# motordriver.net
KiCad netlist of a schematic drawn in EAGLE
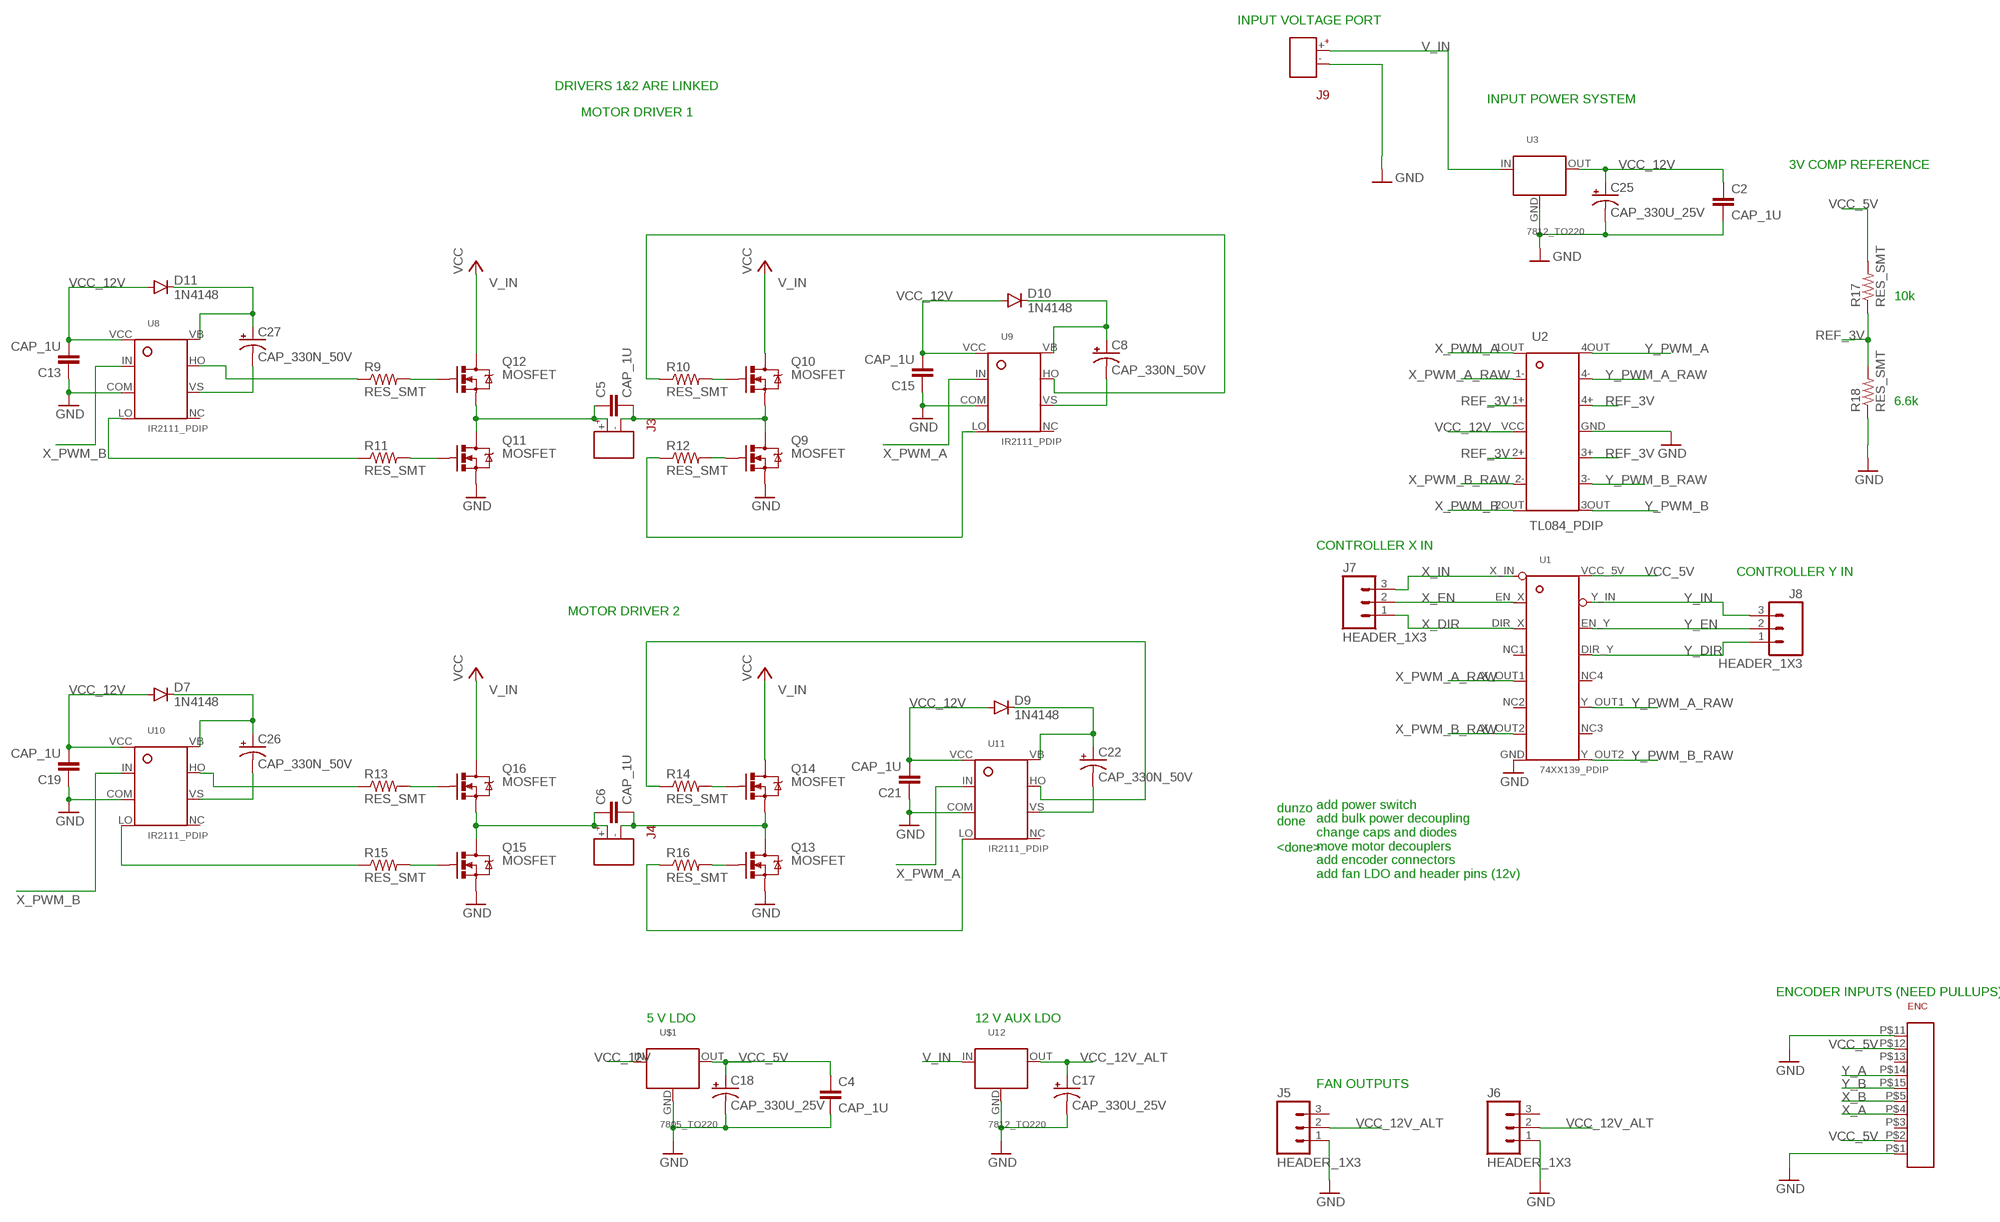
[diagram p0: schematic, sheet 1, part 1 of 2]
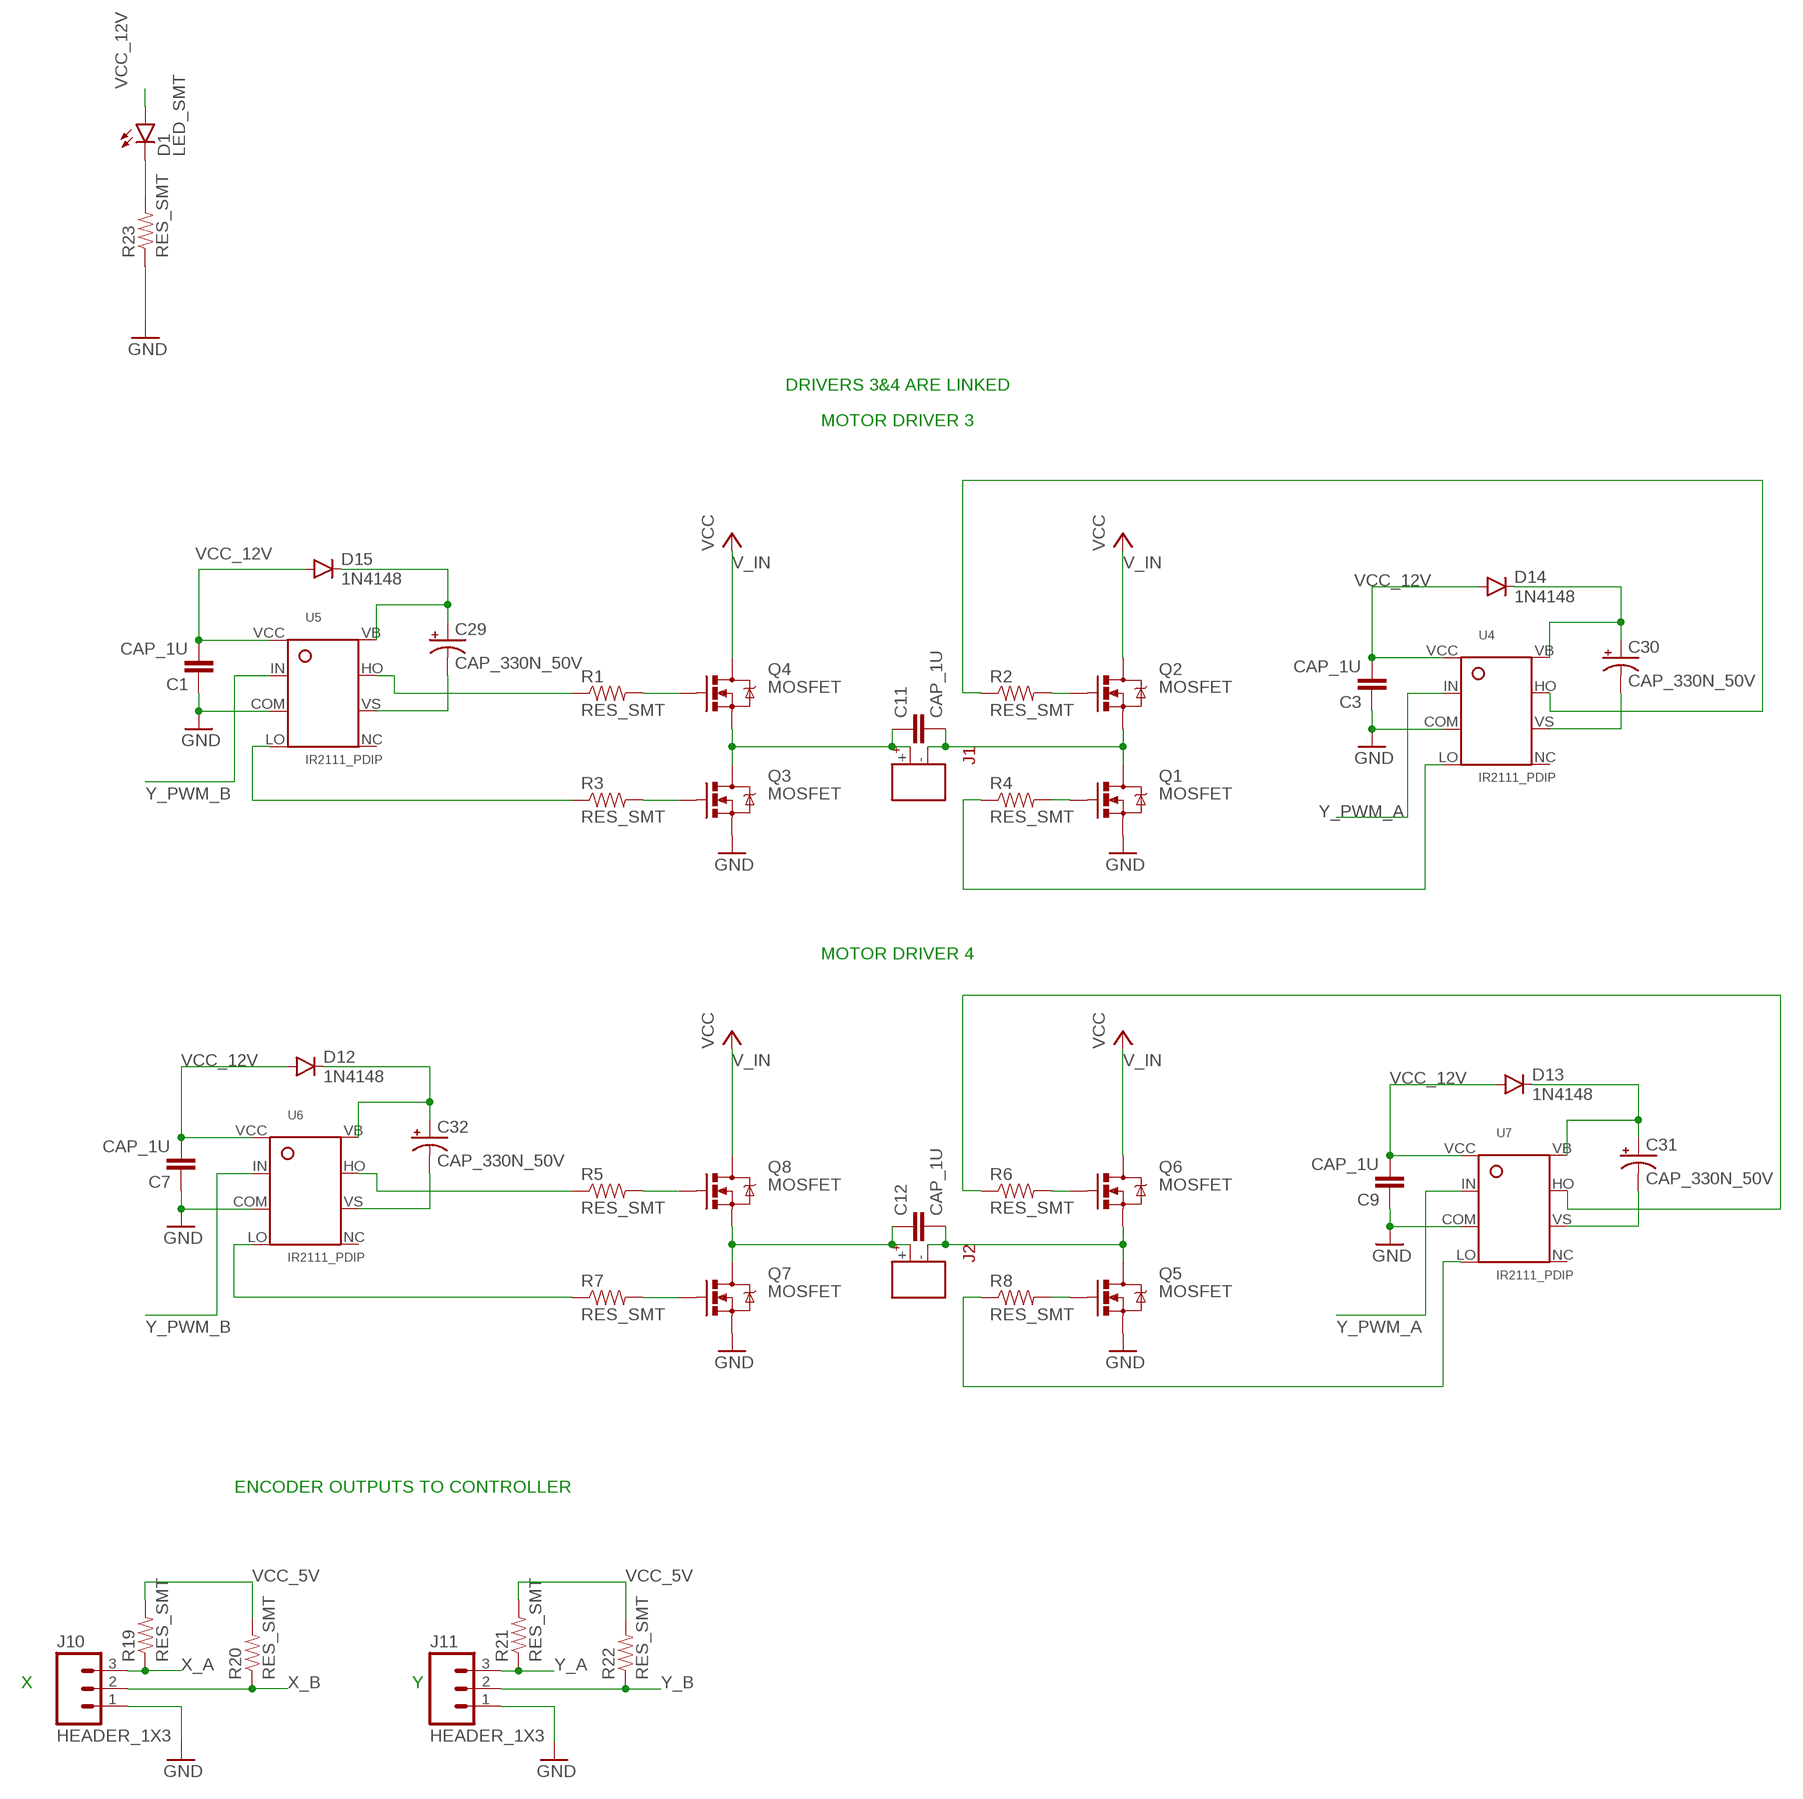
[diagram p1: schematic, sheet 1, part 2 of 2]

(export (version "E")
  (design (tool "Eeschema 10.0.6"))
  (components
    (comp (ref "C1")
      (value "CAP_1U")
      (footprint "eagle-import:2DIP")
      (libsource (lib "eagle-import") (part "CAP_1U"))
    )
    (comp (ref "C2")
      (value "CAP_1U")
      (footprint "eagle-import:2DIP")
      (libsource (lib "eagle-import") (part "CAP_1U"))
    )
    (comp (ref "C3")
      (value "CAP_1U")
      (footprint "eagle-import:2DIP")
      (libsource (lib "eagle-import") (part "CAP_1U"))
    )
    (comp (ref "C4")
      (value "CAP_1U")
      (footprint "eagle-import:2DIP")
      (libsource (lib "eagle-import") (part "CAP_1U"))
    )
    (comp (ref "C5")
      (value "CAP_1U")
      (footprint "eagle-import:2DIP")
      (libsource (lib "eagle-import") (part "CAP_1U"))
    )
    (comp (ref "C6")
      (value "CAP_1U")
      (footprint "eagle-import:2DIP")
      (libsource (lib "eagle-import") (part "CAP_1U"))
    )
    (comp (ref "C7")
      (value "CAP_1U")
      (footprint "eagle-import:2DIP")
      (libsource (lib "eagle-import") (part "CAP_1U"))
    )
    (comp (ref "C8")
      (value "CAP_330N_50V")
      (footprint "eagle-import:RADIAL_5")
      (libsource (lib "eagle-import") (part "CAP_330N_50V"))
    )
    (comp (ref "C9")
      (value "CAP_1U")
      (footprint "eagle-import:2DIP")
      (libsource (lib "eagle-import") (part "CAP_1U"))
    )
    (comp (ref "C11")
      (value "CAP_1U")
      (footprint "eagle-import:2DIP")
      (libsource (lib "eagle-import") (part "CAP_1U"))
    )
    (comp (ref "C12")
      (value "CAP_1U")
      (footprint "eagle-import:2DIP")
      (libsource (lib "eagle-import") (part "CAP_1U"))
    )
    (comp (ref "C13")
      (value "CAP_1U")
      (footprint "eagle-import:2DIP")
      (libsource (lib "eagle-import") (part "CAP_1U"))
    )
    (comp (ref "C15")
      (value "CAP_1U")
      (footprint "eagle-import:2DIP")
      (libsource (lib "eagle-import") (part "CAP_1U"))
    )
    (comp (ref "C17")
      (value "CAP_330U_25V")
      (footprint "eagle-import:RADIAL_1O")
      (libsource (lib "eagle-import") (part "CAP_330U_25V"))
    )
    (comp (ref "C18")
      (value "CAP_330U_25V")
      (footprint "eagle-import:RADIAL_1O")
      (libsource (lib "eagle-import") (part "CAP_330U_25V"))
    )
    (comp (ref "C19")
      (value "CAP_1U")
      (footprint "eagle-import:2DIP")
      (libsource (lib "eagle-import") (part "CAP_1U"))
    )
    (comp (ref "C21")
      (value "CAP_1U")
      (footprint "eagle-import:2DIP")
      (libsource (lib "eagle-import") (part "CAP_1U"))
    )
    (comp (ref "C22")
      (value "CAP_330N_50V")
      (footprint "eagle-import:RADIAL_5")
      (libsource (lib "eagle-import") (part "CAP_330N_50V"))
    )
    (comp (ref "C25")
      (value "CAP_330U_25V")
      (footprint "eagle-import:RADIAL_1O")
      (libsource (lib "eagle-import") (part "CAP_330U_25V"))
    )
    (comp (ref "C26")
      (value "CAP_330N_50V")
      (footprint "eagle-import:RADIAL_5")
      (libsource (lib "eagle-import") (part "CAP_330N_50V"))
    )
    (comp (ref "C27")
      (value "CAP_330N_50V")
      (footprint "eagle-import:RADIAL_5")
      (libsource (lib "eagle-import") (part "CAP_330N_50V"))
    )
    (comp (ref "C29")
      (value "CAP_330N_50V")
      (footprint "eagle-import:RADIAL_5")
      (libsource (lib "eagle-import") (part "CAP_330N_50V"))
    )
    (comp (ref "C30")
      (value "CAP_330N_50V")
      (footprint "eagle-import:RADIAL_5")
      (libsource (lib "eagle-import") (part "CAP_330N_50V"))
    )
    (comp (ref "C31")
      (value "CAP_330N_50V")
      (footprint "eagle-import:RADIAL_5")
      (libsource (lib "eagle-import") (part "CAP_330N_50V"))
    )
    (comp (ref "C32")
      (value "CAP_330N_50V")
      (footprint "eagle-import:RADIAL_5")
      (libsource (lib "eagle-import") (part "CAP_330N_50V"))
    )
    (comp (ref "D1")
      (value "LED_SMT")
      (footprint "eagle-import:LED_0603")
      (libsource (lib "eagle-import") (part "LED_SMT"))
    )
    (comp (ref "D7")
      (value "1N4148")
      (footprint "eagle-import:1N4148")
      (libsource (lib "eagle-import") (part "1N4148"))
    )
    (comp (ref "D9")
      (value "1N4148")
      (footprint "eagle-import:1N4148")
      (libsource (lib "eagle-import") (part "1N4148"))
    )
    (comp (ref "D10")
      (value "1N4148")
      (footprint "eagle-import:1N4148")
      (libsource (lib "eagle-import") (part "1N4148"))
    )
    (comp (ref "D11")
      (value "1N4148")
      (footprint "eagle-import:1N4148")
      (libsource (lib "eagle-import") (part "1N4148"))
    )
    (comp (ref "D12")
      (value "1N4148")
      (footprint "eagle-import:1N4148")
      (libsource (lib "eagle-import") (part "1N4148"))
    )
    (comp (ref "D13")
      (value "1N4148")
      (footprint "eagle-import:1N4148")
      (libsource (lib "eagle-import") (part "1N4148"))
    )
    (comp (ref "D14")
      (value "1N4148")
      (footprint "eagle-import:1N4148")
      (libsource (lib "eagle-import") (part "1N4148"))
    )
    (comp (ref "D15")
      (value "1N4148")
      (footprint "eagle-import:1N4148")
      (libsource (lib "eagle-import") (part "1N4148"))
    )
    (comp (ref "ENC")
      (value "CONN_5X2")
      (footprint "eagle-import:CONN_5X2")
      (libsource (lib "eagle-import") (part "CONN_5X2"))
    )
    (comp (ref "J1")
      (value "CONNECTOR_MOTORS")
      (footprint "eagle-import:CONN_MOTOR")
      (libsource (lib "eagle-import") (part "CONNECTOR_MOTORS"))
    )
    (comp (ref "J2")
      (value "CONNECTOR_MOTORS")
      (footprint "eagle-import:CONN_MOTOR")
      (libsource (lib "eagle-import") (part "CONNECTOR_MOTORS"))
    )
    (comp (ref "J3")
      (value "CONNECTOR_MOTORS")
      (footprint "eagle-import:CONN_MOTOR")
      (libsource (lib "eagle-import") (part "CONNECTOR_MOTORS"))
    )
    (comp (ref "J4")
      (value "CONNECTOR_MOTORS")
      (footprint "eagle-import:CONN_MOTOR")
      (libsource (lib "eagle-import") (part "CONNECTOR_MOTORS"))
    )
    (comp (ref "J5")
      (value "HEADER_1X3")
      (footprint "eagle-import:HEADER_1X3")
      (libsource (lib "eagle-import") (part "HEADER_1X3"))
    )
    (comp (ref "J6")
      (value "HEADER_1X3")
      (footprint "eagle-import:HEADER_1X3")
      (libsource (lib "eagle-import") (part "HEADER_1X3"))
    )
    (comp (ref "J7")
      (value "HEADER_1X3")
      (footprint "eagle-import:HEADER_1X3")
      (libsource (lib "eagle-import") (part "HEADER_1X3"))
    )
    (comp (ref "J8")
      (value "HEADER_1X3")
      (footprint "eagle-import:HEADER_1X3")
      (libsource (lib "eagle-import") (part "HEADER_1X3"))
    )
    (comp (ref "J9")
      (value "CONNECTOR_MOTORS")
      (footprint "eagle-import:CONN_MOTOR")
      (libsource (lib "eagle-import") (part "CONNECTOR_MOTORS"))
    )
    (comp (ref "J10")
      (value "HEADER_1X3")
      (footprint "eagle-import:HEADER_1X3")
      (libsource (lib "eagle-import") (part "HEADER_1X3"))
    )
    (comp (ref "J11")
      (value "HEADER_1X3")
      (footprint "eagle-import:HEADER_1X3")
      (libsource (lib "eagle-import") (part "HEADER_1X3"))
    )
    (comp (ref "Q1")
      (value "MOSFET")
      (footprint "eagle-import:MOSFET")
      (libsource (lib "eagle-import") (part "MOSFET"))
    )
    (comp (ref "Q2")
      (value "MOSFET")
      (footprint "eagle-import:MOSFET")
      (libsource (lib "eagle-import") (part "MOSFET"))
    )
    (comp (ref "Q3")
      (value "MOSFET")
      (footprint "eagle-import:MOSFET")
      (libsource (lib "eagle-import") (part "MOSFET"))
    )
    (comp (ref "Q4")
      (value "MOSFET")
      (footprint "eagle-import:MOSFET")
      (libsource (lib "eagle-import") (part "MOSFET"))
    )
    (comp (ref "Q5")
      (value "MOSFET")
      (footprint "eagle-import:MOSFET")
      (libsource (lib "eagle-import") (part "MOSFET"))
    )
    (comp (ref "Q6")
      (value "MOSFET")
      (footprint "eagle-import:MOSFET")
      (libsource (lib "eagle-import") (part "MOSFET"))
    )
    (comp (ref "Q7")
      (value "MOSFET")
      (footprint "eagle-import:MOSFET")
      (libsource (lib "eagle-import") (part "MOSFET"))
    )
    (comp (ref "Q8")
      (value "MOSFET")
      (footprint "eagle-import:MOSFET")
      (libsource (lib "eagle-import") (part "MOSFET"))
    )
    (comp (ref "Q9")
      (value "MOSFET")
      (footprint "eagle-import:MOSFET")
      (libsource (lib "eagle-import") (part "MOSFET"))
    )
    (comp (ref "Q10")
      (value "MOSFET")
      (footprint "eagle-import:MOSFET")
      (libsource (lib "eagle-import") (part "MOSFET"))
    )
    (comp (ref "Q11")
      (value "MOSFET")
      (footprint "eagle-import:MOSFET")
      (libsource (lib "eagle-import") (part "MOSFET"))
    )
    (comp (ref "Q12")
      (value "MOSFET")
      (footprint "eagle-import:MOSFET")
      (libsource (lib "eagle-import") (part "MOSFET"))
    )
    (comp (ref "Q13")
      (value "MOSFET")
      (footprint "eagle-import:MOSFET")
      (libsource (lib "eagle-import") (part "MOSFET"))
    )
    (comp (ref "Q14")
      (value "MOSFET")
      (footprint "eagle-import:MOSFET")
      (libsource (lib "eagle-import") (part "MOSFET"))
    )
    (comp (ref "Q15")
      (value "MOSFET")
      (footprint "eagle-import:MOSFET")
      (libsource (lib "eagle-import") (part "MOSFET"))
    )
    (comp (ref "Q16")
      (value "MOSFET")
      (footprint "eagle-import:MOSFET")
      (libsource (lib "eagle-import") (part "MOSFET"))
    )
    (comp (ref "R1")
      (value "RES_SMT")
      (footprint "eagle-import:0603")
      (libsource (lib "eagle-import") (part "RES_SMT"))
    )
    (comp (ref "R2")
      (value "RES_SMT")
      (footprint "eagle-import:0603")
      (libsource (lib "eagle-import") (part "RES_SMT"))
    )
    (comp (ref "R3")
      (value "RES_SMT")
      (footprint "eagle-import:0603")
      (libsource (lib "eagle-import") (part "RES_SMT"))
    )
    (comp (ref "R4")
      (value "RES_SMT")
      (footprint "eagle-import:0603")
      (libsource (lib "eagle-import") (part "RES_SMT"))
    )
    (comp (ref "R5")
      (value "RES_SMT")
      (footprint "eagle-import:0603")
      (libsource (lib "eagle-import") (part "RES_SMT"))
    )
    (comp (ref "R6")
      (value "RES_SMT")
      (footprint "eagle-import:0603")
      (libsource (lib "eagle-import") (part "RES_SMT"))
    )
    (comp (ref "R7")
      (value "RES_SMT")
      (footprint "eagle-import:0603")
      (libsource (lib "eagle-import") (part "RES_SMT"))
    )
    (comp (ref "R8")
      (value "RES_SMT")
      (footprint "eagle-import:0603")
      (libsource (lib "eagle-import") (part "RES_SMT"))
    )
    (comp (ref "R9")
      (value "RES_SMT")
      (footprint "eagle-import:0603")
      (libsource (lib "eagle-import") (part "RES_SMT"))
    )
    (comp (ref "R10")
      (value "RES_SMT")
      (footprint "eagle-import:0603")
      (libsource (lib "eagle-import") (part "RES_SMT"))
    )
    (comp (ref "R11")
      (value "RES_SMT")
      (footprint "eagle-import:0603")
      (libsource (lib "eagle-import") (part "RES_SMT"))
    )
    (comp (ref "R12")
      (value "RES_SMT")
      (footprint "eagle-import:0603")
      (libsource (lib "eagle-import") (part "RES_SMT"))
    )
    (comp (ref "R13")
      (value "RES_SMT")
      (footprint "eagle-import:0603")
      (libsource (lib "eagle-import") (part "RES_SMT"))
    )
    (comp (ref "R14")
      (value "RES_SMT")
      (footprint "eagle-import:0603")
      (libsource (lib "eagle-import") (part "RES_SMT"))
    )
    (comp (ref "R15")
      (value "RES_SMT")
      (footprint "eagle-import:0603")
      (libsource (lib "eagle-import") (part "RES_SMT"))
    )
    (comp (ref "R16")
      (value "RES_SMT")
      (footprint "eagle-import:0603")
      (libsource (lib "eagle-import") (part "RES_SMT"))
    )
    (comp (ref "R17")
      (value "RES_SMT")
      (footprint "eagle-import:0603")
      (libsource (lib "eagle-import") (part "RES_SMT"))
    )
    (comp (ref "R18")
      (value "RES_SMT")
      (footprint "eagle-import:0603")
      (libsource (lib "eagle-import") (part "RES_SMT"))
    )
    (comp (ref "R19")
      (value "RES_SMT")
      (footprint "eagle-import:0603")
      (libsource (lib "eagle-import") (part "RES_SMT"))
    )
    (comp (ref "R20")
      (value "RES_SMT")
      (footprint "eagle-import:0603")
      (libsource (lib "eagle-import") (part "RES_SMT"))
    )
    (comp (ref "R21")
      (value "RES_SMT")
      (footprint "eagle-import:0603")
      (libsource (lib "eagle-import") (part "RES_SMT"))
    )
    (comp (ref "R22")
      (value "RES_SMT")
      (footprint "eagle-import:0603")
      (libsource (lib "eagle-import") (part "RES_SMT"))
    )
    (comp (ref "R23")
      (value "RES_SMT")
      (footprint "eagle-import:0603")
      (libsource (lib "eagle-import") (part "RES_SMT"))
    )
    (comp (ref "U$1")
      (value "7805_TO220")
      (footprint "eagle-import:TO-220")
      (libsource (lib "eagle-import") (part "7805_TO220"))
    )
    (comp (ref "U1")
      (value "74XX139_PDIP")
      (footprint "eagle-import:16PDIP")
      (libsource (lib "eagle-import") (part "74XX139_PDIP"))
    )
    (comp (ref "U2")
      (value "TL084_PDIP")
      (footprint "eagle-import:14PDIP")
      (libsource (lib "eagle-import") (part "TL084_PDIP"))
    )
    (comp (ref "U3")
      (value "7812_TO220")
      (footprint "eagle-import:TO-220")
      (libsource (lib "eagle-import") (part "7812_TO220"))
    )
    (comp (ref "U4")
      (value "IR2111_PDIP")
      (footprint "eagle-import:8PDIP")
      (libsource (lib "eagle-import") (part "IR2111_PDIP"))
    )
    (comp (ref "U5")
      (value "IR2111_PDIP")
      (footprint "eagle-import:8PDIP")
      (libsource (lib "eagle-import") (part "IR2111_PDIP"))
    )
    (comp (ref "U6")
      (value "IR2111_PDIP")
      (footprint "eagle-import:8PDIP")
      (libsource (lib "eagle-import") (part "IR2111_PDIP"))
    )
    (comp (ref "U7")
      (value "IR2111_PDIP")
      (footprint "eagle-import:8PDIP")
      (libsource (lib "eagle-import") (part "IR2111_PDIP"))
    )
    (comp (ref "U8")
      (value "IR2111_PDIP")
      (footprint "eagle-import:8PDIP")
      (libsource (lib "eagle-import") (part "IR2111_PDIP"))
    )
    (comp (ref "U9")
      (value "IR2111_PDIP")
      (footprint "eagle-import:8PDIP")
      (libsource (lib "eagle-import") (part "IR2111_PDIP"))
    )
    (comp (ref "U10")
      (value "IR2111_PDIP")
      (footprint "eagle-import:8PDIP")
      (libsource (lib "eagle-import") (part "IR2111_PDIP"))
    )
    (comp (ref "U11")
      (value "IR2111_PDIP")
      (footprint "eagle-import:8PDIP")
      (libsource (lib "eagle-import") (part "IR2111_PDIP"))
    )
    (comp (ref "U12")
      (value "7812_TO220")
      (footprint "eagle-import:TO-220")
      (libsource (lib "eagle-import") (part "7812_TO220"))
    )
  )
  (nets
    (net (code "1") (name "/REF_3V") (class "Default")
      (node (ref "R17") (pin "1") (pinfunction "1_1") (pintype "passive"))
      (node (ref "R18") (pin "2") (pinfunction "2_2") (pintype "passive"))
      (node (ref "U2") (pin "1+") (pinfunction "1+_1+") (pintype "bidirectional"))
      (node (ref "U2") (pin "2+") (pinfunction "2+_2+") (pintype "bidirectional"))
      (node (ref "U2") (pin "3+") (pinfunction "3+_3+") (pintype "bidirectional"))
      (node (ref "U2") (pin "4+") (pinfunction "4+_4+") (pintype "bidirectional"))
    )
    (net (code "2") (name "/VCC_5V") (class "Default")
      (node (ref "C18") (pin "+") (pinfunction "+_+") (pintype "passive"))
      (node (ref "C4") (pin "P$1") (pinfunction "1_P$1") (pintype "passive"))
      (node (ref "ENC") (pin "P$12") (pinfunction "P$9_P$12") (pintype "bidirectional"))
      (node (ref "ENC") (pin "P$2") (pinfunction "P$2_P$2") (pintype "bidirectional"))
      (node (ref "R17") (pin "2") (pinfunction "2_2") (pintype "passive"))
      (node (ref "R19") (pin "2") (pinfunction "2_2") (pintype "passive"))
      (node (ref "R20") (pin "2") (pinfunction "2_2") (pintype "passive"))
      (node (ref "R21") (pin "2") (pinfunction "2_2") (pintype "passive"))
      (node (ref "R22") (pin "2") (pinfunction "2_2") (pintype "passive"))
      (node (ref "U$1") (pin "OUT") (pinfunction "OUT_OUT") (pintype "bidirectional"))
      (node (ref "U1") (pin "VCC_5V") (pinfunction "P$16_VCC_5V") (pintype "bidirectional"))
    )
    (net (code "3") (name "/VCC_12V") (class "Default")
      (node (ref "C1") (pin "P$2") (pinfunction "2_P$2") (pintype "passive"))
      (node (ref "C13") (pin "P$2") (pinfunction "2_P$2") (pintype "passive"))
      (node (ref "C15") (pin "P$2") (pinfunction "2_P$2") (pintype "passive"))
      (node (ref "C19") (pin "P$2") (pinfunction "2_P$2") (pintype "passive"))
      (node (ref "C2") (pin "P$1") (pinfunction "1_P$1") (pintype "passive"))
      (node (ref "C21") (pin "P$2") (pinfunction "2_P$2") (pintype "passive"))
      (node (ref "C25") (pin "+") (pinfunction "+_+") (pintype "passive"))
      (node (ref "C3") (pin "P$2") (pinfunction "2_P$2") (pintype "passive"))
      (node (ref "C7") (pin "P$2") (pinfunction "2_P$2") (pintype "passive"))
      (node (ref "C9") (pin "P$2") (pinfunction "2_P$2") (pintype "passive"))
      (node (ref "D1") (pin "A") (pinfunction "A_A") (pintype "passive"))
      (node (ref "D10") (pin "A") (pinfunction "A_A") (pintype "passive"))
      (node (ref "D11") (pin "A") (pinfunction "A_A") (pintype "passive"))
      (node (ref "D12") (pin "A") (pinfunction "A_A") (pintype "passive"))
      (node (ref "D13") (pin "A") (pinfunction "A_A") (pintype "passive"))
      (node (ref "D14") (pin "A") (pinfunction "A_A") (pintype "passive"))
      (node (ref "D15") (pin "A") (pinfunction "A_A") (pintype "passive"))
      (node (ref "D7") (pin "A") (pinfunction "A_A") (pintype "passive"))
      (node (ref "D9") (pin "A") (pinfunction "A_A") (pintype "passive"))
      (node (ref "U$1") (pin "IN") (pinfunction "IN_IN") (pintype "bidirectional"))
      (node (ref "U10") (pin "VCC") (pinfunction "P$1_VCC") (pintype "bidirectional"))
      (node (ref "U11") (pin "VCC") (pinfunction "P$1_VCC") (pintype "bidirectional"))
      (node (ref "U2") (pin "VCC") (pinfunction "VCC_VCC") (pintype "bidirectional"))
      (node (ref "U3") (pin "OUT") (pinfunction "OUT_OUT") (pintype "bidirectional"))
      (node (ref "U4") (pin "VCC") (pinfunction "P$1_VCC") (pintype "bidirectional"))
      (node (ref "U5") (pin "VCC") (pinfunction "P$1_VCC") (pintype "bidirectional"))
      (node (ref "U6") (pin "VCC") (pinfunction "P$1_VCC") (pintype "bidirectional"))
      (node (ref "U7") (pin "VCC") (pinfunction "P$1_VCC") (pintype "bidirectional"))
      (node (ref "U8") (pin "VCC") (pinfunction "P$1_VCC") (pintype "bidirectional"))
      (node (ref "U9") (pin "VCC") (pinfunction "P$1_VCC") (pintype "bidirectional"))
    )
    (net (code "4") (name "/VCC_12V_ALT") (class "Default")
      (node (ref "C17") (pin "+") (pinfunction "+_+") (pintype "passive"))
      (node (ref "J5") (pin "2") (pinfunction "2_2") (pintype "passive"))
      (node (ref "J6") (pin "2") (pinfunction "2_2") (pintype "passive"))
      (node (ref "U12") (pin "OUT") (pinfunction "OUT_OUT") (pintype "bidirectional"))
    )
    (net (code "5") (name "/X_A") (class "Default")
      (node (ref "ENC") (pin "P$4") (pinfunction "P$4_P$4") (pintype "bidirectional"))
      (node (ref "J10") (pin "3") (pinfunction "3_3") (pintype "passive"))
      (node (ref "R19") (pin "1") (pinfunction "1_1") (pintype "passive"))
    )
    (net (code "6") (name "/X_B") (class "Default")
      (node (ref "ENC") (pin "P$5") (pinfunction "P$5_P$5") (pintype "bidirectional"))
      (node (ref "J10") (pin "2") (pinfunction "2_2") (pintype "passive"))
      (node (ref "R20") (pin "1") (pinfunction "1_1") (pintype "passive"))
    )
    (net (code "7") (name "/X_DIR") (class "Default")
      (node (ref "J7") (pin "1") (pinfunction "1_1") (pintype "passive"))
      (node (ref "U1") (pin "DIR_X") (pinfunction "P$3_DIR_X") (pintype "bidirectional"))
    )
    (net (code "8") (name "/X_EN") (class "Default")
      (node (ref "J7") (pin "2") (pinfunction "2_2") (pintype "passive"))
      (node (ref "U1") (pin "EN_X") (pinfunction "P$2_EN_X") (pintype "bidirectional"))
    )
    (net (code "9") (name "/X_IN") (class "Default")
      (node (ref "J7") (pin "3") (pinfunction "3_3") (pintype "passive"))
      (node (ref "U1") (pin "X_IN") (pinfunction "P$1_X_IN") (pintype "bidirectional"))
    )
    (net (code "10") (name "/X_PWM_A") (class "Default")
      (node (ref "U11") (pin "IN") (pinfunction "P$2_IN") (pintype "bidirectional"))
      (node (ref "U2") (pin "1OUT") (pinfunction "OUT1_1OUT") (pintype "bidirectional"))
      (node (ref "U9") (pin "IN") (pinfunction "P$2_IN") (pintype "bidirectional"))
    )
    (net (code "11") (name "/X_PWM_A_RAW") (class "Default")
      (node (ref "U1") (pin "X_OUT1") (pinfunction "P$5_X_OUT1") (pintype "bidirectional"))
      (node (ref "U2") (pin "1-") (pinfunction "1-_1-") (pintype "bidirectional"))
    )
    (net (code "12") (name "/X_PWM_B") (class "Default")
      (node (ref "U10") (pin "IN") (pinfunction "P$2_IN") (pintype "bidirectional"))
      (node (ref "U2") (pin "2OUT") (pinfunction "OUT2_2OUT") (pintype "bidirectional"))
      (node (ref "U8") (pin "IN") (pinfunction "P$2_IN") (pintype "bidirectional"))
    )
    (net (code "13") (name "/X_PWM_B_RAW") (class "Default")
      (node (ref "U1") (pin "X_OUT2") (pinfunction "P$7_X_OUT2") (pintype "bidirectional"))
      (node (ref "U2") (pin "2-") (pinfunction "2-_2-") (pintype "bidirectional"))
    )
    (net (code "14") (name "/Y_A") (class "Default")
      (node (ref "ENC") (pin "P$14") (pinfunction "P$7_P$14") (pintype "bidirectional"))
      (node (ref "J11") (pin "3") (pinfunction "3_3") (pintype "passive"))
      (node (ref "R21") (pin "1") (pinfunction "1_1") (pintype "passive"))
    )
    (net (code "15") (name "/Y_B") (class "Default")
      (node (ref "ENC") (pin "P$15") (pinfunction "P$6_P$15") (pintype "bidirectional"))
      (node (ref "J11") (pin "2") (pinfunction "2_2") (pintype "passive"))
      (node (ref "R22") (pin "1") (pinfunction "1_1") (pintype "passive"))
    )
    (net (code "16") (name "/Y_DIR") (class "Default")
      (node (ref "J8") (pin "1") (pinfunction "1_1") (pintype "passive"))
      (node (ref "U1") (pin "DIR_Y") (pinfunction "P$13_DIR_Y") (pintype "bidirectional"))
    )
    (net (code "17") (name "/Y_EN") (class "Default")
      (node (ref "J8") (pin "2") (pinfunction "2_2") (pintype "passive"))
      (node (ref "U1") (pin "EN_Y") (pinfunction "P$14_EN_Y") (pintype "bidirectional"))
    )
    (net (code "18") (name "/Y_IN") (class "Default")
      (node (ref "J8") (pin "3") (pinfunction "3_3") (pintype "passive"))
      (node (ref "U1") (pin "Y_IN") (pinfunction "P$15_Y_IN") (pintype "bidirectional"))
    )
    (net (code "19") (name "/Y_PWM_A") (class "Default")
      (node (ref "U2") (pin "4OUT") (pinfunction "OUT4_4OUT") (pintype "bidirectional"))
      (node (ref "U4") (pin "IN") (pinfunction "P$2_IN") (pintype "bidirectional"))
      (node (ref "U7") (pin "IN") (pinfunction "P$2_IN") (pintype "bidirectional"))
    )
    (net (code "20") (name "/Y_PWM_A_RAW") (class "Default")
      (node (ref "U1") (pin "Y_OUT1") (pinfunction "P$11_Y_OUT1") (pintype "bidirectional"))
      (node (ref "U2") (pin "4-") (pinfunction "4-_4-") (pintype "bidirectional"))
    )
    (net (code "21") (name "/Y_PWM_B") (class "Default")
      (node (ref "U2") (pin "3OUT") (pinfunction "OUT3_3OUT") (pintype "bidirectional"))
      (node (ref "U5") (pin "IN") (pinfunction "P$2_IN") (pintype "bidirectional"))
      (node (ref "U6") (pin "IN") (pinfunction "P$2_IN") (pintype "bidirectional"))
    )
    (net (code "22") (name "/Y_PWM_B_RAW") (class "Default")
      (node (ref "U1") (pin "Y_OUT2") (pinfunction "P$9_Y_OUT2") (pintype "bidirectional"))
      (node (ref "U2") (pin "3-") (pinfunction "3-_3-") (pintype "bidirectional"))
    )
    (net (code "23") (name "GND") (class "Default")
      (node (ref "C1") (pin "P$1") (pinfunction "1_P$1") (pintype "passive"))
      (node (ref "C13") (pin "P$1") (pinfunction "1_P$1") (pintype "passive"))
      (node (ref "C15") (pin "P$1") (pinfunction "1_P$1") (pintype "passive"))
      (node (ref "C17") (pin "-") (pinfunction "-_-") (pintype "passive"))
      (node (ref "C18") (pin "-") (pinfunction "-_-") (pintype "passive"))
      (node (ref "C19") (pin "P$1") (pinfunction "1_P$1") (pintype "passive"))
      (node (ref "C2") (pin "P$2") (pinfunction "2_P$2") (pintype "passive"))
      (node (ref "C21") (pin "P$1") (pinfunction "1_P$1") (pintype "passive"))
      (node (ref "C25") (pin "-") (pinfunction "-_-") (pintype "passive"))
      (node (ref "C3") (pin "P$1") (pinfunction "1_P$1") (pintype "passive"))
      (node (ref "C4") (pin "P$2") (pinfunction "2_P$2") (pintype "passive"))
      (node (ref "C7") (pin "P$1") (pinfunction "1_P$1") (pintype "passive"))
      (node (ref "C9") (pin "P$1") (pinfunction "1_P$1") (pintype "passive"))
      (node (ref "ENC") (pin "P$1") (pinfunction "P$1_P$1") (pintype "bidirectional"))
      (node (ref "ENC") (pin "P$11") (pinfunction "P$10_P$11") (pintype "bidirectional"))
      (node (ref "J10") (pin "1") (pinfunction "1_1") (pintype "passive"))
      (node (ref "J11") (pin "1") (pinfunction "1_1") (pintype "passive"))
      (node (ref "J5") (pin "1") (pinfunction "1_1") (pintype "passive"))
      (node (ref "J6") (pin "1") (pinfunction "1_1") (pintype "passive"))
      (node (ref "J9") (pin "-") (pinfunction "-_-") (pintype "bidirectional"))
      (node (ref "Q1") (pin "S") (pinfunction "S_S") (pintype "passive"))
      (node (ref "Q11") (pin "S") (pinfunction "S_S") (pintype "passive"))
      (node (ref "Q13") (pin "S") (pinfunction "S_S") (pintype "passive"))
      (node (ref "Q15") (pin "S") (pinfunction "S_S") (pintype "passive"))
      (node (ref "Q3") (pin "S") (pinfunction "S_S") (pintype "passive"))
      (node (ref "Q5") (pin "S") (pinfunction "S_S") (pintype "passive"))
      (node (ref "Q7") (pin "S") (pinfunction "S_S") (pintype "passive"))
      (node (ref "Q9") (pin "S") (pinfunction "S_S") (pintype "passive"))
      (node (ref "R18") (pin "1") (pinfunction "1_1") (pintype "passive"))
      (node (ref "R23") (pin "1") (pinfunction "1_1") (pintype "passive"))
      (node (ref "U$1") (pin "GND") (pinfunction "GND_GND") (pintype "bidirectional"))
      (node (ref "U1") (pin "GND") (pinfunction "P$8_GND") (pintype "bidirectional"))
      (node (ref "U10") (pin "COM") (pinfunction "P$3_COM") (pintype "bidirectional"))
      (node (ref "U11") (pin "COM") (pinfunction "P$3_COM") (pintype "bidirectional"))
      (node (ref "U12") (pin "GND") (pinfunction "GND_GND") (pintype "bidirectional"))
      (node (ref "U2") (pin "GND") (pinfunction "GND_GND") (pintype "bidirectional"))
      (node (ref "U3") (pin "GND") (pinfunction "GND_GND") (pintype "bidirectional"))
      (node (ref "U4") (pin "COM") (pinfunction "P$3_COM") (pintype "bidirectional"))
      (node (ref "U5") (pin "COM") (pinfunction "P$3_COM") (pintype "bidirectional"))
      (node (ref "U6") (pin "COM") (pinfunction "P$3_COM") (pintype "bidirectional"))
      (node (ref "U7") (pin "COM") (pinfunction "P$3_COM") (pintype "bidirectional"))
      (node (ref "U8") (pin "COM") (pinfunction "P$3_COM") (pintype "bidirectional"))
      (node (ref "U9") (pin "COM") (pinfunction "P$3_COM") (pintype "bidirectional"))
    )
    (net (code "24") (name "Net-(C5-1)") (class "Default")
      (node (ref "C5") (pin "P$1") (pinfunction "1_P$1") (pintype "passive"))
      (node (ref "J3") (pin "+") (pinfunction "+_+") (pintype "bidirectional"))
      (node (ref "Q11") (pin "D") (pinfunction "D_D") (pintype "passive"))
      (node (ref "Q12") (pin "S") (pinfunction "S_S") (pintype "passive"))
    )
    (net (code "25") (name "Net-(C5-2)") (class "Default")
      (node (ref "C5") (pin "P$2") (pinfunction "2_P$2") (pintype "passive"))
      (node (ref "J3") (pin "-") (pinfunction "-_-") (pintype "bidirectional"))
      (node (ref "Q10") (pin "S") (pinfunction "S_S") (pintype "passive"))
      (node (ref "Q9") (pin "D") (pinfunction "D_D") (pintype "passive"))
    )
    (net (code "26") (name "Net-(C6-1)") (class "Default")
      (node (ref "C6") (pin "P$1") (pinfunction "1_P$1") (pintype "passive"))
      (node (ref "J4") (pin "+") (pinfunction "+_+") (pintype "bidirectional"))
      (node (ref "Q15") (pin "D") (pinfunction "D_D") (pintype "passive"))
      (node (ref "Q16") (pin "S") (pinfunction "S_S") (pintype "passive"))
    )
    (net (code "27") (name "Net-(C6-2)") (class "Default")
      (node (ref "C6") (pin "P$2") (pinfunction "2_P$2") (pintype "passive"))
      (node (ref "J4") (pin "-") (pinfunction "-_-") (pintype "bidirectional"))
      (node (ref "Q13") (pin "D") (pinfunction "D_D") (pintype "passive"))
      (node (ref "Q14") (pin "S") (pinfunction "S_S") (pintype "passive"))
    )
    (net (code "28") (name "Net-(C11-1)") (class "Default")
      (node (ref "C11") (pin "P$1") (pinfunction "1_P$1") (pintype "passive"))
      (node (ref "J1") (pin "+") (pinfunction "+_+") (pintype "bidirectional"))
      (node (ref "Q3") (pin "D") (pinfunction "D_D") (pintype "passive"))
      (node (ref "Q4") (pin "S") (pinfunction "S_S") (pintype "passive"))
    )
    (net (code "29") (name "Net-(C11-2)") (class "Default")
      (node (ref "C11") (pin "P$2") (pinfunction "2_P$2") (pintype "passive"))
      (node (ref "J1") (pin "-") (pinfunction "-_-") (pintype "bidirectional"))
      (node (ref "Q1") (pin "D") (pinfunction "D_D") (pintype "passive"))
      (node (ref "Q2") (pin "S") (pinfunction "S_S") (pintype "passive"))
    )
    (net (code "30") (name "Net-(C12-1)") (class "Default")
      (node (ref "C12") (pin "P$1") (pinfunction "1_P$1") (pintype "passive"))
      (node (ref "J2") (pin "+") (pinfunction "+_+") (pintype "bidirectional"))
      (node (ref "Q7") (pin "D") (pinfunction "D_D") (pintype "passive"))
      (node (ref "Q8") (pin "S") (pinfunction "S_S") (pintype "passive"))
    )
    (net (code "31") (name "Net-(C12-2)") (class "Default")
      (node (ref "C12") (pin "P$2") (pinfunction "2_P$2") (pintype "passive"))
      (node (ref "J2") (pin "-") (pinfunction "-_-") (pintype "bidirectional"))
      (node (ref "Q5") (pin "D") (pinfunction "D_D") (pintype "passive"))
      (node (ref "Q6") (pin "S") (pinfunction "S_S") (pintype "passive"))
    )
    (net (code "32") (name "Net-(D1-PadC)") (class "Default")
      (node (ref "D1") (pin "C") (pinfunction "C_C") (pintype "passive"))
      (node (ref "R23") (pin "2") (pinfunction "2_2") (pintype "passive"))
    )
    (net (code "33") (name "Net-(Q1-PadG)") (class "Default")
      (node (ref "Q1") (pin "G") (pinfunction "G_G") (pintype "passive"))
      (node (ref "R4") (pin "2") (pinfunction "2_2") (pintype "passive"))
    )
    (net (code "34") (name "Net-(Q2-PadG)") (class "Default")
      (node (ref "Q2") (pin "G") (pinfunction "G_G") (pintype "passive"))
      (node (ref "R2") (pin "2") (pinfunction "2_2") (pintype "passive"))
    )
    (net (code "35") (name "Net-(Q3-PadG)") (class "Default")
      (node (ref "Q3") (pin "G") (pinfunction "G_G") (pintype "passive"))
      (node (ref "R3") (pin "2") (pinfunction "2_2") (pintype "passive"))
    )
    (net (code "36") (name "Net-(Q4-PadG)") (class "Default")
      (node (ref "Q4") (pin "G") (pinfunction "G_G") (pintype "passive"))
      (node (ref "R1") (pin "2") (pinfunction "2_2") (pintype "passive"))
    )
    (net (code "37") (name "Net-(Q5-PadG)") (class "Default")
      (node (ref "Q5") (pin "G") (pinfunction "G_G") (pintype "passive"))
      (node (ref "R8") (pin "2") (pinfunction "2_2") (pintype "passive"))
    )
    (net (code "38") (name "Net-(Q6-PadG)") (class "Default")
      (node (ref "Q6") (pin "G") (pinfunction "G_G") (pintype "passive"))
      (node (ref "R6") (pin "2") (pinfunction "2_2") (pintype "passive"))
    )
    (net (code "39") (name "Net-(Q7-PadG)") (class "Default")
      (node (ref "Q7") (pin "G") (pinfunction "G_G") (pintype "passive"))
      (node (ref "R7") (pin "2") (pinfunction "2_2") (pintype "passive"))
    )
    (net (code "40") (name "Net-(Q8-PadG)") (class "Default")
      (node (ref "Q8") (pin "G") (pinfunction "G_G") (pintype "passive"))
      (node (ref "R5") (pin "2") (pinfunction "2_2") (pintype "passive"))
    )
    (net (code "41") (name "Net-(Q9-PadG)") (class "Default")
      (node (ref "Q9") (pin "G") (pinfunction "G_G") (pintype "passive"))
      (node (ref "R12") (pin "2") (pinfunction "2_2") (pintype "passive"))
    )
    (net (code "42") (name "Net-(Q10-PadG)") (class "Default")
      (node (ref "Q10") (pin "G") (pinfunction "G_G") (pintype "passive"))
      (node (ref "R10") (pin "2") (pinfunction "2_2") (pintype "passive"))
    )
    (net (code "43") (name "Net-(Q11-PadG)") (class "Default")
      (node (ref "Q11") (pin "G") (pinfunction "G_G") (pintype "passive"))
      (node (ref "R11") (pin "2") (pinfunction "2_2") (pintype "passive"))
    )
    (net (code "44") (name "Net-(Q12-PadG)") (class "Default")
      (node (ref "Q12") (pin "G") (pinfunction "G_G") (pintype "passive"))
      (node (ref "R9") (pin "2") (pinfunction "2_2") (pintype "passive"))
    )
    (net (code "45") (name "Net-(Q13-PadG)") (class "Default")
      (node (ref "Q13") (pin "G") (pinfunction "G_G") (pintype "passive"))
      (node (ref "R16") (pin "2") (pinfunction "2_2") (pintype "passive"))
    )
    (net (code "46") (name "Net-(Q14-PadG)") (class "Default")
      (node (ref "Q14") (pin "G") (pinfunction "G_G") (pintype "passive"))
      (node (ref "R14") (pin "2") (pinfunction "2_2") (pintype "passive"))
    )
    (net (code "47") (name "Net-(Q15-PadG)") (class "Default")
      (node (ref "Q15") (pin "G") (pinfunction "G_G") (pintype "passive"))
      (node (ref "R15") (pin "2") (pinfunction "2_2") (pintype "passive"))
    )
    (net (code "48") (name "Net-(Q16-PadG)") (class "Default")
      (node (ref "Q16") (pin "G") (pinfunction "G_G") (pintype "passive"))
      (node (ref "R13") (pin "2") (pinfunction "2_2") (pintype "passive"))
    )
    (net (code "49") (name "Net-(U4-P$4)") (class "Default")
      (node (ref "R4") (pin "1") (pinfunction "1_1") (pintype "passive"))
      (node (ref "U4") (pin "LO") (pinfunction "P$4_LO") (pintype "bidirectional"))
    )
    (net (code "50") (name "Net-(U4-P$6)") (class "Default")
      (node (ref "C30") (pin "-") (pinfunction "-_-") (pintype "passive"))
      (node (ref "U4") (pin "VS") (pinfunction "P$6_VS") (pintype "bidirectional"))
    )
    (net (code "51") (name "Net-(U4-P$7)") (class "Default")
      (node (ref "R2") (pin "1") (pinfunction "1_1") (pintype "passive"))
      (node (ref "U4") (pin "HO") (pinfunction "P$7_HO") (pintype "bidirectional"))
    )
    (net (code "52") (name "Net-(U4-P$8)") (class "Default")
      (node (ref "C30") (pin "+") (pinfunction "+_+") (pintype "passive"))
      (node (ref "D14") (pin "C") (pinfunction "C_C") (pintype "passive"))
      (node (ref "U4") (pin "VB") (pinfunction "P$8_VB") (pintype "bidirectional"))
    )
    (net (code "53") (name "Net-(U5-P$4)") (class "Default")
      (node (ref "R3") (pin "1") (pinfunction "1_1") (pintype "passive"))
      (node (ref "U5") (pin "LO") (pinfunction "P$4_LO") (pintype "bidirectional"))
    )
    (net (code "54") (name "Net-(U5-P$6)") (class "Default")
      (node (ref "C29") (pin "-") (pinfunction "-_-") (pintype "passive"))
      (node (ref "U5") (pin "VS") (pinfunction "P$6_VS") (pintype "bidirectional"))
    )
    (net (code "55") (name "Net-(U5-P$7)") (class "Default")
      (node (ref "R1") (pin "1") (pinfunction "1_1") (pintype "passive"))
      (node (ref "U5") (pin "HO") (pinfunction "P$7_HO") (pintype "bidirectional"))
    )
    (net (code "56") (name "Net-(U5-P$8)") (class "Default")
      (node (ref "C29") (pin "+") (pinfunction "+_+") (pintype "passive"))
      (node (ref "D15") (pin "C") (pinfunction "C_C") (pintype "passive"))
      (node (ref "U5") (pin "VB") (pinfunction "P$8_VB") (pintype "bidirectional"))
    )
    (net (code "57") (name "Net-(U6-P$4)") (class "Default")
      (node (ref "R7") (pin "1") (pinfunction "1_1") (pintype "passive"))
      (node (ref "U6") (pin "LO") (pinfunction "P$4_LO") (pintype "bidirectional"))
    )
    (net (code "58") (name "Net-(U6-P$6)") (class "Default")
      (node (ref "C32") (pin "-") (pinfunction "-_-") (pintype "passive"))
      (node (ref "U6") (pin "VS") (pinfunction "P$6_VS") (pintype "bidirectional"))
    )
    (net (code "59") (name "Net-(U6-P$7)") (class "Default")
      (node (ref "R5") (pin "1") (pinfunction "1_1") (pintype "passive"))
      (node (ref "U6") (pin "HO") (pinfunction "P$7_HO") (pintype "bidirectional"))
    )
    (net (code "60") (name "Net-(U6-P$8)") (class "Default")
      (node (ref "C32") (pin "+") (pinfunction "+_+") (pintype "passive"))
      (node (ref "D12") (pin "C") (pinfunction "C_C") (pintype "passive"))
      (node (ref "U6") (pin "VB") (pinfunction "P$8_VB") (pintype "bidirectional"))
    )
    (net (code "61") (name "Net-(U7-P$4)") (class "Default")
      (node (ref "R8") (pin "1") (pinfunction "1_1") (pintype "passive"))
      (node (ref "U7") (pin "LO") (pinfunction "P$4_LO") (pintype "bidirectional"))
    )
    (net (code "62") (name "Net-(U7-P$6)") (class "Default")
      (node (ref "C31") (pin "-") (pinfunction "-_-") (pintype "passive"))
      (node (ref "U7") (pin "VS") (pinfunction "P$6_VS") (pintype "bidirectional"))
    )
    (net (code "63") (name "Net-(U7-P$7)") (class "Default")
      (node (ref "R6") (pin "1") (pinfunction "1_1") (pintype "passive"))
      (node (ref "U7") (pin "HO") (pinfunction "P$7_HO") (pintype "bidirectional"))
    )
    (net (code "64") (name "Net-(U7-P$8)") (class "Default")
      (node (ref "C31") (pin "+") (pinfunction "+_+") (pintype "passive"))
      (node (ref "D13") (pin "C") (pinfunction "C_C") (pintype "passive"))
      (node (ref "U7") (pin "VB") (pinfunction "P$8_VB") (pintype "bidirectional"))
    )
    (net (code "65") (name "Net-(U8-P$4)") (class "Default")
      (node (ref "R11") (pin "1") (pinfunction "1_1") (pintype "passive"))
      (node (ref "U8") (pin "LO") (pinfunction "P$4_LO") (pintype "bidirectional"))
    )
    (net (code "66") (name "Net-(U8-P$6)") (class "Default")
      (node (ref "C27") (pin "-") (pinfunction "-_-") (pintype "passive"))
      (node (ref "U8") (pin "VS") (pinfunction "P$6_VS") (pintype "bidirectional"))
    )
    (net (code "67") (name "Net-(U8-P$7)") (class "Default")
      (node (ref "R9") (pin "1") (pinfunction "1_1") (pintype "passive"))
      (node (ref "U8") (pin "HO") (pinfunction "P$7_HO") (pintype "bidirectional"))
    )
    (net (code "68") (name "Net-(U8-P$8)") (class "Default")
      (node (ref "C27") (pin "+") (pinfunction "+_+") (pintype "passive"))
      (node (ref "D11") (pin "C") (pinfunction "C_C") (pintype "passive"))
      (node (ref "U8") (pin "VB") (pinfunction "P$8_VB") (pintype "bidirectional"))
    )
    (net (code "69") (name "Net-(U9-P$4)") (class "Default")
      (node (ref "R12") (pin "1") (pinfunction "1_1") (pintype "passive"))
      (node (ref "U9") (pin "LO") (pinfunction "P$4_LO") (pintype "bidirectional"))
    )
    (net (code "70") (name "Net-(U9-P$6)") (class "Default")
      (node (ref "C8") (pin "-") (pinfunction "-_-") (pintype "passive"))
      (node (ref "U9") (pin "VS") (pinfunction "P$6_VS") (pintype "bidirectional"))
    )
    (net (code "71") (name "Net-(U9-P$7)") (class "Default")
      (node (ref "R10") (pin "1") (pinfunction "1_1") (pintype "passive"))
      (node (ref "U9") (pin "HO") (pinfunction "P$7_HO") (pintype "bidirectional"))
    )
    (net (code "72") (name "Net-(U9-P$8)") (class "Default")
      (node (ref "C8") (pin "+") (pinfunction "+_+") (pintype "passive"))
      (node (ref "D10") (pin "C") (pinfunction "C_C") (pintype "passive"))
      (node (ref "U9") (pin "VB") (pinfunction "P$8_VB") (pintype "bidirectional"))
    )
    (net (code "73") (name "Net-(U10-P$4)") (class "Default")
      (node (ref "R15") (pin "1") (pinfunction "1_1") (pintype "passive"))
      (node (ref "U10") (pin "LO") (pinfunction "P$4_LO") (pintype "bidirectional"))
    )
    (net (code "74") (name "Net-(U10-P$6)") (class "Default")
      (node (ref "C26") (pin "-") (pinfunction "-_-") (pintype "passive"))
      (node (ref "U10") (pin "VS") (pinfunction "P$6_VS") (pintype "bidirectional"))
    )
    (net (code "75") (name "Net-(U10-P$7)") (class "Default")
      (node (ref "R13") (pin "1") (pinfunction "1_1") (pintype "passive"))
      (node (ref "U10") (pin "HO") (pinfunction "P$7_HO") (pintype "bidirectional"))
    )
    (net (code "76") (name "Net-(U10-P$8)") (class "Default")
      (node (ref "C26") (pin "+") (pinfunction "+_+") (pintype "passive"))
      (node (ref "D7") (pin "C") (pinfunction "C_C") (pintype "passive"))
      (node (ref "U10") (pin "VB") (pinfunction "P$8_VB") (pintype "bidirectional"))
    )
    (net (code "77") (name "Net-(U11-P$4)") (class "Default")
      (node (ref "R16") (pin "1") (pinfunction "1_1") (pintype "passive"))
      (node (ref "U11") (pin "LO") (pinfunction "P$4_LO") (pintype "bidirectional"))
    )
    (net (code "78") (name "Net-(U11-P$6)") (class "Default")
      (node (ref "C22") (pin "-") (pinfunction "-_-") (pintype "passive"))
      (node (ref "U11") (pin "VS") (pinfunction "P$6_VS") (pintype "bidirectional"))
    )
    (net (code "79") (name "Net-(U11-P$7)") (class "Default")
      (node (ref "R14") (pin "1") (pinfunction "1_1") (pintype "passive"))
      (node (ref "U11") (pin "HO") (pinfunction "P$7_HO") (pintype "bidirectional"))
    )
    (net (code "80") (name "Net-(U11-P$8)") (class "Default")
      (node (ref "C22") (pin "+") (pinfunction "+_+") (pintype "passive"))
      (node (ref "D9") (pin "C") (pinfunction "C_C") (pintype "passive"))
      (node (ref "U11") (pin "VB") (pinfunction "P$8_VB") (pintype "bidirectional"))
    )
    (net (code "81") (name "VCC") (class "Default")
      (node (ref "J9") (pin "+") (pinfunction "+_+") (pintype "bidirectional"))
      (node (ref "Q10") (pin "D") (pinfunction "D_D") (pintype "passive"))
      (node (ref "Q12") (pin "D") (pinfunction "D_D") (pintype "passive"))
      (node (ref "Q14") (pin "D") (pinfunction "D_D") (pintype "passive"))
      (node (ref "Q16") (pin "D") (pinfunction "D_D") (pintype "passive"))
      (node (ref "Q2") (pin "D") (pinfunction "D_D") (pintype "passive"))
      (node (ref "Q4") (pin "D") (pinfunction "D_D") (pintype "passive"))
      (node (ref "Q6") (pin "D") (pinfunction "D_D") (pintype "passive"))
      (node (ref "Q8") (pin "D") (pinfunction "D_D") (pintype "passive"))
      (node (ref "U12") (pin "IN") (pinfunction "IN_IN") (pintype "bidirectional"))
      (node (ref "U3") (pin "IN") (pinfunction "IN_IN") (pintype "bidirectional"))
    )
    (net (code "82") (name "unconnected-(ENC-P$8-PadP$13)") (class "Default")
      (node (ref "ENC") (pin "P$13") (pinfunction "P$8_P$13") (pintype "bidirectional"))
    )
    (net (code "83") (name "unconnected-(ENC-PadP$3)") (class "Default")
      (node (ref "ENC") (pin "P$3") (pinfunction "P$3_P$3") (pintype "bidirectional"))
    )
    (net (code "84") (name "unconnected-(J5-Pad3)") (class "Default")
      (node (ref "J5") (pin "3") (pinfunction "3_3") (pintype "passive"))
    )
    (net (code "85") (name "unconnected-(J6-Pad3)") (class "Default")
      (node (ref "J6") (pin "3") (pinfunction "3_3") (pintype "passive"))
    )
    (net (code "86") (name "unconnected-(U1-P$4-PadNC1)") (class "Default")
      (node (ref "U1") (pin "NC1") (pinfunction "P$4_NC1") (pintype "bidirectional"))
    )
    (net (code "87") (name "unconnected-(U1-P$6-PadNC2)") (class "Default")
      (node (ref "U1") (pin "NC2") (pinfunction "P$6_NC2") (pintype "bidirectional"))
    )
    (net (code "88") (name "unconnected-(U1-P$10-PadNC3)") (class "Default")
      (node (ref "U1") (pin "NC3") (pinfunction "P$10_NC3") (pintype "bidirectional"))
    )
    (net (code "89") (name "unconnected-(U1-P$12-PadNC4)") (class "Default")
      (node (ref "U1") (pin "NC4") (pinfunction "P$12_NC4") (pintype "bidirectional"))
    )
    (net (code "90") (name "unconnected-(U4-P$5-PadNC)") (class "Default")
      (node (ref "U4") (pin "NC") (pinfunction "P$5_NC") (pintype "bidirectional"))
    )
    (net (code "91") (name "unconnected-(U5-P$5-PadNC)") (class "Default")
      (node (ref "U5") (pin "NC") (pinfunction "P$5_NC") (pintype "bidirectional"))
    )
    (net (code "92") (name "unconnected-(U6-P$5-PadNC)") (class "Default")
      (node (ref "U6") (pin "NC") (pinfunction "P$5_NC") (pintype "bidirectional"))
    )
    (net (code "93") (name "unconnected-(U7-P$5-PadNC)") (class "Default")
      (node (ref "U7") (pin "NC") (pinfunction "P$5_NC") (pintype "bidirectional"))
    )
    (net (code "94") (name "unconnected-(U8-P$5-PadNC)") (class "Default")
      (node (ref "U8") (pin "NC") (pinfunction "P$5_NC") (pintype "bidirectional"))
    )
    (net (code "95") (name "unconnected-(U9-P$5-PadNC)") (class "Default")
      (node (ref "U9") (pin "NC") (pinfunction "P$5_NC") (pintype "bidirectional"))
    )
    (net (code "96") (name "unconnected-(U10-P$5-PadNC)") (class "Default")
      (node (ref "U10") (pin "NC") (pinfunction "P$5_NC") (pintype "bidirectional"))
    )
    (net (code "97") (name "unconnected-(U11-P$5-PadNC)") (class "Default")
      (node (ref "U11") (pin "NC") (pinfunction "P$5_NC") (pintype "bidirectional"))
    )
  )
)
